# 13_USB.net
KiCad netlist of a schematic drawn in Altium Designer
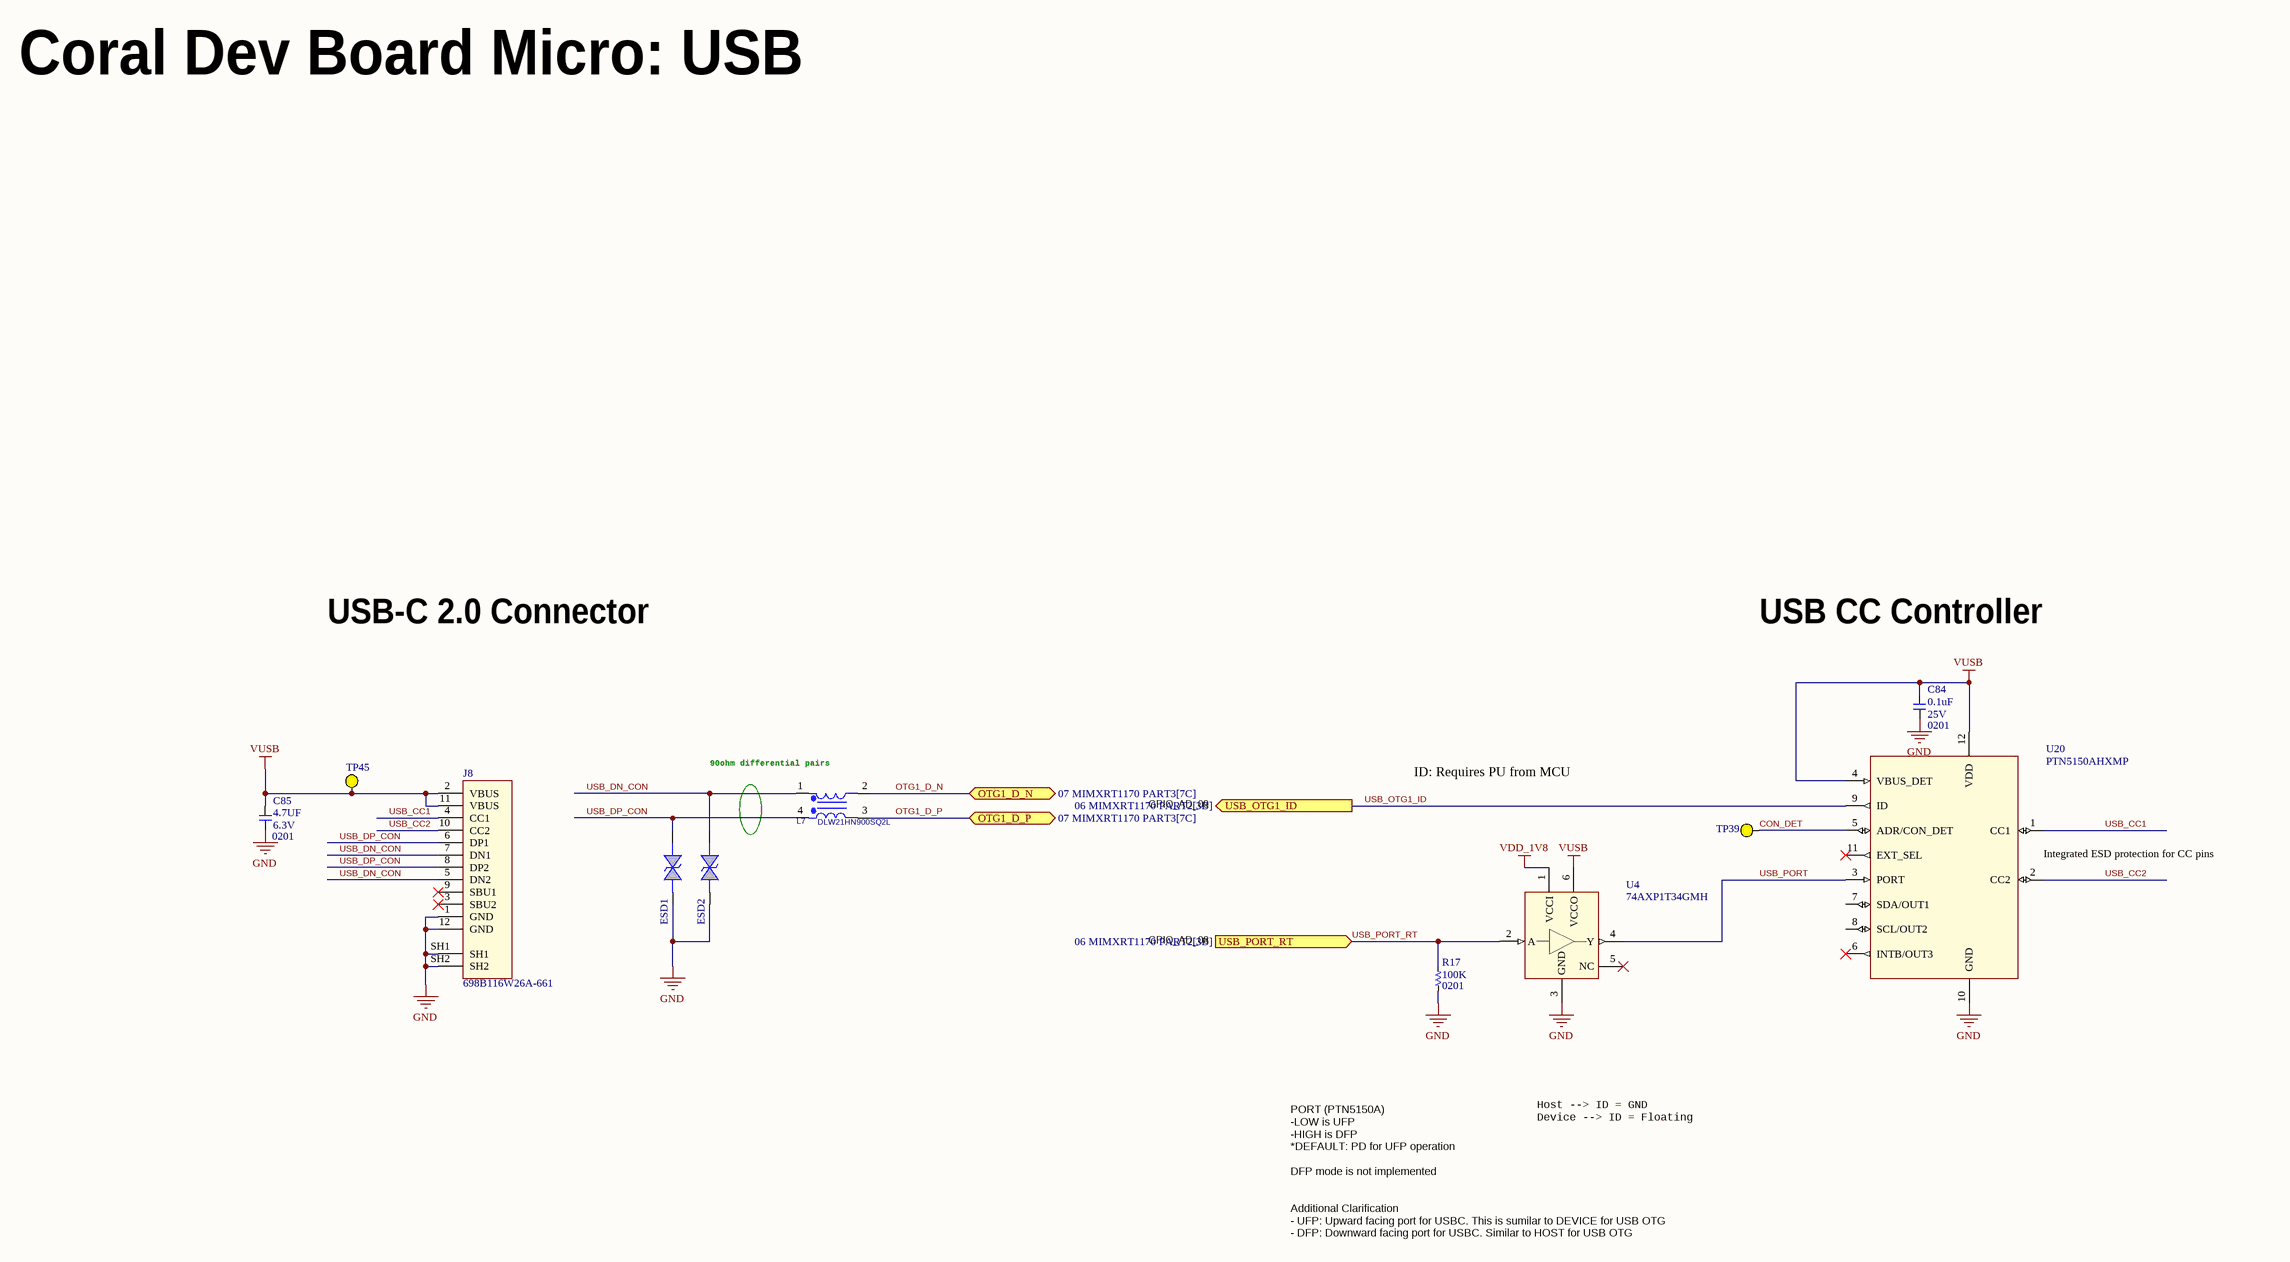
[diagram p0: 13 USB.SchDoc]

(export (version "E")
  (design (tool "Eeschema 10.0.6"))
  (components
    (comp (ref "C84")
      (value "0.1uF")
      (footprint "C0201Y")
      (description "CAP, CER, X5R, 0.1uF, 25V, 20%, 0201, 0.33mm T")
      (fields
        (field (name "MFG") "MURATA")
        (field (name "PACKAGE") "0201")
        (field (name "VOLTAGE") "25V")
        (field (name "TOLERANCE") "20%")
      )
      (libsource (lib "AltiumReleaseLibDB") (part "__Template_Cap"))
    )
    (comp (ref "C85")
      (value "4.7UF")
      (footprint "C0201Y")
      (description "CAP, CER, X5R, 4.7uF, 20%, 6.3V, 0201")
      (fields
        (field (name "MFG") "MURATA")
        (field (name "PACKAGE") "0201")
        (field (name "VOLTAGE") "6.3V")
        (field (name "TOLERANCE") "20%")
      )
      (libsource (lib "AltiumReleaseLibDB") (part "__Template_Cap"))
    )
    (comp (ref "ESD1")
      (value "3.5pF/5V")
      (footprint "0201")
      (description "DIODE TVS 15kV 10V 50A 8pF SMT RoHS")
      (fields (field (name "MPN") "DESD5V0V1BCSP-7"))
      (libsource (lib "links") (part "DIODE BI-DIR TRIG"))
    )
    (comp (ref "ESD2")
      (value "3.5pF/5V")
      (footprint "0201")
      (description "DIODE TVS 15kV 10V 50A 8pF SMT RoHS")
      (fields (field (name "MPN") "DESD5V0V1BCSP-7"))
      (libsource (lib "links") (part "DIODE BI-DIR TRIG"))
    )
    (comp (ref "J8")
      (value "~")
      (footprint "EDAC_698B116W26A-661")
      (description "CONN, USB-C, RCPT, RA, USB 2.0, 16 P, 0.5MM PITCH, GOLD, SMT")
      (fields (field (name "MFG") "EDAC Inc") (field (name "MFG P/N") "698B116W26A-661"))
      (libsource (lib "AltiumReleaseLibDB") (part "CONN_EDAC_690-W16-290T131"))
    )
    (comp (ref "L7")
      (value "DLW21HN900SQ2L")
      (footprint "IND4_CHOKE_0805")
      (description "IND CHK 90 OHM@100MHZ 330MA 25% 0805")
      (libsource (lib "SpacePark") (part "IND_CMC_DLW21"))
    )
    (comp (ref "R17")
      (value "100K")
      (footprint "R0201")
      (description "RES, 100K, 1%, 1/20W, 0201")
      (fields (field (name "MFG") "PANASONIC") (field (name "PACKAGE") "0201") (field (name "POWER") "1/20W"))
      (libsource (lib "AltiumReleaseLibDB") (part "__Template_Resistor"))
    )
    (comp (ref "TP39")
      (value "TESTPAD_30MIL")
      (footprint "TESTPAD_SMT_30MIL")
      (description "TESTPAD_SMT_30MIL")
      (fields (field (name "MFG") "_PCB Feature"))
      (libsource (lib "AltiumReleaseLibDB") (part "TESTPAD_30MIL"))
    )
    (comp (ref "TP45")
      (value "TESTPAD_30MIL")
      (footprint "TESTPAD_SMT_30MIL")
      (description "TESTPAD_SMT_30MIL")
      (fields (field (name "MFG") "_PCB Feature"))
      (libsource (lib "AltiumReleaseLibDB") (part "TESTPAD_30MIL"))
    )
    (comp (ref "U4")
      (value "TRANSLATOR_74AXP1T34GMH")
      (footprint "SON50P145X100X50-6")
      (description "IC, TRANSLATOR, 74AXP1, UNIDIR, 1-CH, NON-INVERTED O/P, LOW NOISE OVERSHOOT, XSON-6")
      (fields (field (name "MFG") "Nexperia USA Inc.") (field (name "MFG P/N") "74AXP1T34GMH"))
      (libsource (lib "AltiumReleaseLibDB") (part "TRANSLATOR_74AXP1T34GMH"))
    )
    (comp (ref "U20")
      (value "CONTROLLER_PTN5150AHXMP")
      (footprint "X2QFN12_1.6X1.6MMM")
      (description "IC, HOST CTLR, PTN5150A, USB, 2.7 TO 5.5 VIN, X2QFN-12")
      (fields (field (name "MFG") "NXP USA Inc.") (field (name "MFG P/N") "PTN5150AHXMP"))
      (libsource (lib "AltiumReleaseLibDB") (part "CONTROLLER_PTN5150AHXMP"))
    )
  )
  (nets
    (net (code "1") (name "/CON_DET") (class "Default")
      (node (ref "TP39") (pin "1") (pintype "passive"))
      (node (ref "U20") (pin "5") (pinfunction "ADR/CON_DET_5") (pintype "bidirectional"))
    )
    (net (code "2") (name "/OTG1_D_N") (class "Default")
      (node (ref "L7") (pin "2") (pinfunction "2_2") (pintype "passive"))
    )
    (net (code "3") (name "/OTG1_D_P") (class "Default")
      (node (ref "L7") (pin "3") (pinfunction "3_3") (pintype "passive"))
    )
    (net (code "4") (name "/USB_CC1") (class "Default")
      (node (ref "J8") (pin "4") (pinfunction "CC1_4") (pintype "passive"))
      (node (ref "U20") (pin "1") (pinfunction "CC1_1") (pintype "bidirectional"))
    )
    (net (code "5") (name "/USB_CC2") (class "Default")
      (node (ref "J8") (pin "10") (pinfunction "CC2_10") (pintype "passive"))
      (node (ref "U20") (pin "2") (pinfunction "CC2_2") (pintype "bidirectional"))
    )
    (net (code "6") (name "/USB_DN_CON") (class "Default")
      (node (ref "ESD2") (pin "2") (pinfunction "2_2") (pintype "passive"))
      (node (ref "J8") (pin "5") (pinfunction "DN2_5") (pintype "passive"))
      (node (ref "J8") (pin "7") (pinfunction "DN1_7") (pintype "power_in"))
      (node (ref "L7") (pin "1") (pinfunction "1_1") (pintype "passive"))
    )
    (net (code "7") (name "/USB_DP_CON") (class "Default")
      (node (ref "ESD1") (pin "2") (pinfunction "2_2") (pintype "passive"))
      (node (ref "J8") (pin "6") (pinfunction "DP1_6") (pintype "passive"))
      (node (ref "J8") (pin "8") (pinfunction "DP2_8") (pintype "power_in"))
      (node (ref "L7") (pin "4") (pinfunction "4_4") (pintype "passive"))
    )
    (net (code "8") (name "/USB_OTG1_ID") (class "Default")
      (node (ref "U20") (pin "9") (pinfunction "ID_9") (pintype "output"))
    )
    (net (code "9") (name "/USB_PORT") (class "Default")
      (node (ref "U20") (pin "3") (pinfunction "PORT_3") (pintype "input"))
      (node (ref "U4") (pin "4") (pinfunction "Y_4") (pintype "output"))
    )
    (net (code "10") (name "/USB_PORT_RT") (class "Default")
      (node (ref "R17") (pin "2") (pintype "passive"))
      (node (ref "U4") (pin "2") (pinfunction "A_2") (pintype "input"))
    )
    (net (code "11") (name "GND") (class "Default")
      (node (ref "C84") (pin "2") (pintype "passive"))
      (node (ref "C85") (pin "2") (pintype "passive"))
      (node (ref "ESD1") (pin "1") (pinfunction "1_1") (pintype "passive"))
      (node (ref "ESD2") (pin "1") (pinfunction "1_1") (pintype "passive"))
      (node (ref "J8") (pin "1") (pinfunction "GND_1") (pintype "power_in"))
      (node (ref "J8") (pin "12") (pinfunction "GND_12") (pintype "power_in"))
      (node (ref "J8") (pin "SH1") (pinfunction "SH1_SH1") (pintype "passive"))
      (node (ref "J8") (pin "SH2") (pinfunction "SH2_SH2") (pintype "passive"))
      (node (ref "R17") (pin "1") (pintype "passive"))
      (node (ref "U20") (pin "10") (pinfunction "GND_10") (pintype "power_in"))
      (node (ref "U4") (pin "3") (pinfunction "GND_3") (pintype "power_in"))
    )
    (net (code "12") (name "VDD_1V8") (class "Default")
      (node (ref "U4") (pin "1") (pinfunction "VCCI_1") (pintype "power_in"))
    )
    (net (code "13") (name "VUSB") (class "Default")
      (node (ref "C84") (pin "1") (pintype "passive"))
      (node (ref "C85") (pin "1") (pintype "passive"))
      (node (ref "J8") (pin "11") (pinfunction "VBUS_11") (pintype "power_in"))
      (node (ref "J8") (pin "2") (pinfunction "VBUS_2") (pintype "power_in"))
      (node (ref "TP45") (pin "1") (pintype "passive"))
      (node (ref "U20") (pin "12") (pinfunction "VDD_12") (pintype "power_in"))
      (node (ref "U20") (pin "4") (pinfunction "VBUS_DET_4") (pintype "input"))
      (node (ref "U4") (pin "6") (pinfunction "VCCO_6") (pintype "power_in"))
    )
    (net (code "14") (name "unconnected-(J8-SBU1-Pad9)") (class "Default")
      (node (ref "J8") (pin "9") (pinfunction "SBU1_9") (pintype "passive+no_connect"))
    )
    (net (code "15") (name "unconnected-(J8-SBU2-Pad3)") (class "Default")
      (node (ref "J8") (pin "3") (pinfunction "SBU2_3") (pintype "passive+no_connect"))
    )
    (net (code "16") (name "unconnected-(U4-NC-Pad5)") (class "Default")
      (node (ref "U4") (pin "5") (pinfunction "NC_5") (pintype "passive+no_connect"))
    )
    (net (code "17") (name "unconnected-(U20-EXT_SEL-Pad11)") (class "Default")
      (node (ref "U20") (pin "11") (pinfunction "EXT_SEL_11") (pintype "output+no_connect"))
    )
    (net (code "18") (name "unconnected-(U20-INTB{slash}OUT3-Pad6)") (class "Default")
      (node (ref "U20") (pin "6") (pinfunction "INTB/OUT3_6") (pintype "output+no_connect"))
    )
    (net (code "19") (name "unconnected-(U20-SCL{slash}OUT2-Pad8)") (class "Default")
      (node (ref "U20") (pin "8") (pinfunction "SCL/OUT2_8") (pintype "bidirectional"))
    )
    (net (code "20") (name "unconnected-(U20-SDA{slash}OUT1-Pad7)") (class "Default")
      (node (ref "U20") (pin "7") (pinfunction "SDA/OUT1_7") (pintype "bidirectional"))
    )
  )
)
